# Hailo_8.net
KiCad netlist of a schematic drawn in Altium Designer
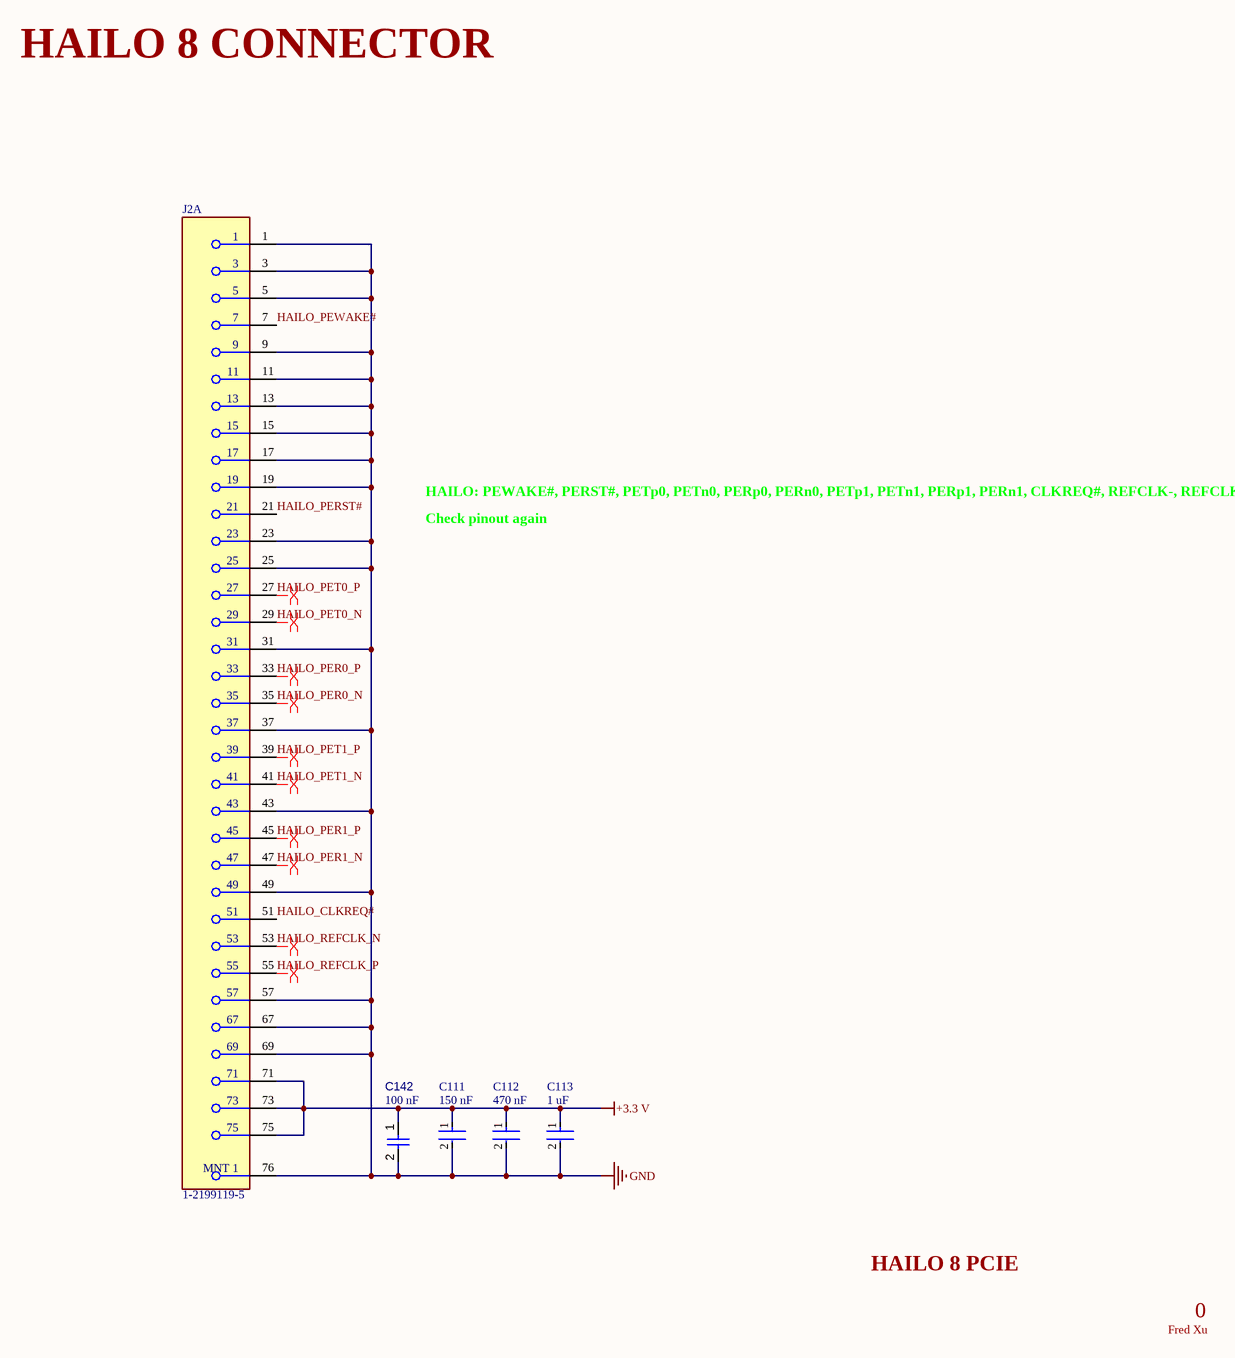
[diagram p0: Hailo 8.SchDoc]

(export (version "E")
  (design (tool "Eeschema 10.0.6"))
  (components
    (comp (ref "C111")
      (value "150 nF")
      (footprint "FP-GCM155-0_05-MFG")
      (description "Ceramic Capacitor for Automotive 150nF ±20% 16VDC X7R 0402 Paper T/R")
      (libsource (lib "Altium Content Vault") (part "02cd4be3c70576c341d710602a673aa"))
    )
    (comp (ref "C112")
      (value "470 nF")
      (footprint "FP-GRM155-0_05-IPC_B")
      (description "Chip Multilayer Ceramic Capacitors for General Purpose, 0402, 0.47uF, X7R, 15%, 20%, 10V")
      (fields (field (name "TOLERANCE") "20%"))
      (libsource (lib "Altium Content Vault") (part "02cd4be3c70576c341d710602a673aa"))
    )
    (comp (ref "C113")
      (value "1 uF")
      (footprint "FP-GCM155-0_2-MFG")
      (description "Ceramic Capacitor for Automotive 1uF ±20% 10VDC X7S 0402 Paper T/R")
      (libsource (lib "Altium Content Vault") (part "11868f565c42a9108669ba33697ecf6"))
    )
    (comp (ref "C142")
      (value "100 nF")
      (footprint "CAPC1005X56X25LL10T15")
      (description "Chip Capacitor, 0.1 uF, +/- 5%, 16 V, 0402 (1005 Metric)")
      (fields (field (name "TOLERANCE") "5%") (field (name "Comment") "0.1 uF"))
      (libsource (lib "Fred Xu") (part "CAP-NP-2"))
    )
    (comp (ref "J2")
      (value "1-2199119-5")
      (footprint "FP-1-2199119-5-MFG")
      (description "CONN M.2 FEMALE 67POS 0.020 GOLD")
      (libsource (lib "Altium Content Vault") (part "7466e0a9e5b4e52356bdad31cee3594"))
    )
  )
  (nets
    (net (code "1") (name "+3.3 V") (class "Default")
      (node (ref "C111") (pin "1") (pinfunction "1_1") (pintype "passive"))
      (node (ref "C112") (pin "1") (pinfunction "1_1") (pintype "passive"))
      (node (ref "C113") (pin "1") (pinfunction "1_1") (pintype "passive"))
      (node (ref "C142") (pin "1") (pinfunction "1_1") (pintype "passive"))
      (node (ref "J2") (pin "71") (pinfunction "71_71") (pintype "passive"))
      (node (ref "J2") (pin "73") (pinfunction "73_73") (pintype "passive"))
      (node (ref "J2") (pin "75") (pinfunction "75_75") (pintype "passive"))
    )
    (net (code "2") (name "/HAILO_CLKREQ#") (class "Default")
      (node (ref "J2") (pin "51") (pinfunction "51_51") (pintype "passive"))
    )
    (net (code "3") (name "/HAILO_PER0_N") (class "Default")
      (node (ref "J2") (pin "35") (pinfunction "35_35") (pintype "passive"))
    )
    (net (code "4") (name "/HAILO_PER0_P") (class "Default")
      (node (ref "J2") (pin "33") (pinfunction "33_33") (pintype "passive"))
    )
    (net (code "5") (name "/HAILO_PER1_N") (class "Default")
      (node (ref "J2") (pin "47") (pinfunction "47_47") (pintype "passive"))
    )
    (net (code "6") (name "/HAILO_PER1_P") (class "Default")
      (node (ref "J2") (pin "45") (pinfunction "45_45") (pintype "passive"))
    )
    (net (code "7") (name "/HAILO_PERST#") (class "Default")
      (node (ref "J2") (pin "21") (pinfunction "21_21") (pintype "passive"))
    )
    (net (code "8") (name "/HAILO_PET0_N") (class "Default")
      (node (ref "J2") (pin "29") (pinfunction "29_29") (pintype "passive"))
    )
    (net (code "9") (name "/HAILO_PET0_P") (class "Default")
      (node (ref "J2") (pin "27") (pinfunction "27_27") (pintype "passive"))
    )
    (net (code "10") (name "/HAILO_PET1_N") (class "Default")
      (node (ref "J2") (pin "41") (pinfunction "41_41") (pintype "passive"))
    )
    (net (code "11") (name "/HAILO_PET1_P") (class "Default")
      (node (ref "J2") (pin "39") (pinfunction "39_39") (pintype "passive"))
    )
    (net (code "12") (name "/HAILO_PEWAKE#") (class "Default")
      (node (ref "J2") (pin "7") (pinfunction "7_7") (pintype "passive"))
    )
    (net (code "13") (name "/HAILO_REFCLK_N") (class "Default")
      (node (ref "J2") (pin "53") (pinfunction "53_53") (pintype "passive"))
    )
    (net (code "14") (name "/HAILO_REFCLK_P") (class "Default")
      (node (ref "J2") (pin "55") (pinfunction "55_55") (pintype "passive"))
    )
    (net (code "15") (name "GND") (class "Default")
      (node (ref "C111") (pin "2") (pinfunction "2_2") (pintype "passive"))
      (node (ref "C112") (pin "2") (pinfunction "2_2") (pintype "passive"))
      (node (ref "C113") (pin "2") (pinfunction "2_2") (pintype "passive"))
      (node (ref "C142") (pin "2") (pinfunction "2_2") (pintype "passive"))
      (node (ref "J2") (pin "1") (pinfunction "1_1") (pintype "passive"))
      (node (ref "J2") (pin "11") (pinfunction "11_11") (pintype "passive"))
      (node (ref "J2") (pin "13") (pinfunction "13_13") (pintype "passive"))
      (node (ref "J2") (pin "15") (pinfunction "15_15") (pintype "passive"))
      (node (ref "J2") (pin "17") (pinfunction "17_17") (pintype "passive"))
      (node (ref "J2") (pin "19") (pinfunction "19_19") (pintype "passive"))
      (node (ref "J2") (pin "23") (pinfunction "23_23") (pintype "passive"))
      (node (ref "J2") (pin "25") (pinfunction "25_25") (pintype "passive"))
      (node (ref "J2") (pin "3") (pinfunction "3_3") (pintype "passive"))
      (node (ref "J2") (pin "31") (pinfunction "31_31") (pintype "passive"))
      (node (ref "J2") (pin "37") (pinfunction "37_37") (pintype "passive"))
      (node (ref "J2") (pin "43") (pinfunction "43_43") (pintype "passive"))
      (node (ref "J2") (pin "49") (pinfunction "49_49") (pintype "passive"))
      (node (ref "J2") (pin "5") (pinfunction "5_5") (pintype "passive"))
      (node (ref "J2") (pin "57") (pinfunction "57_57") (pintype "passive"))
      (node (ref "J2") (pin "67") (pinfunction "67_67") (pintype "passive"))
      (node (ref "J2") (pin "69") (pinfunction "69_69") (pintype "passive"))
      (node (ref "J2") (pin "76") (pinfunction "MNT_1_76") (pintype "passive"))
      (node (ref "J2") (pin "9") (pinfunction "9_9") (pintype "passive"))
    )
  )
)
